# HandschuhProfessionell.net
KiCad netlist of a schematic drawn in EAGLE
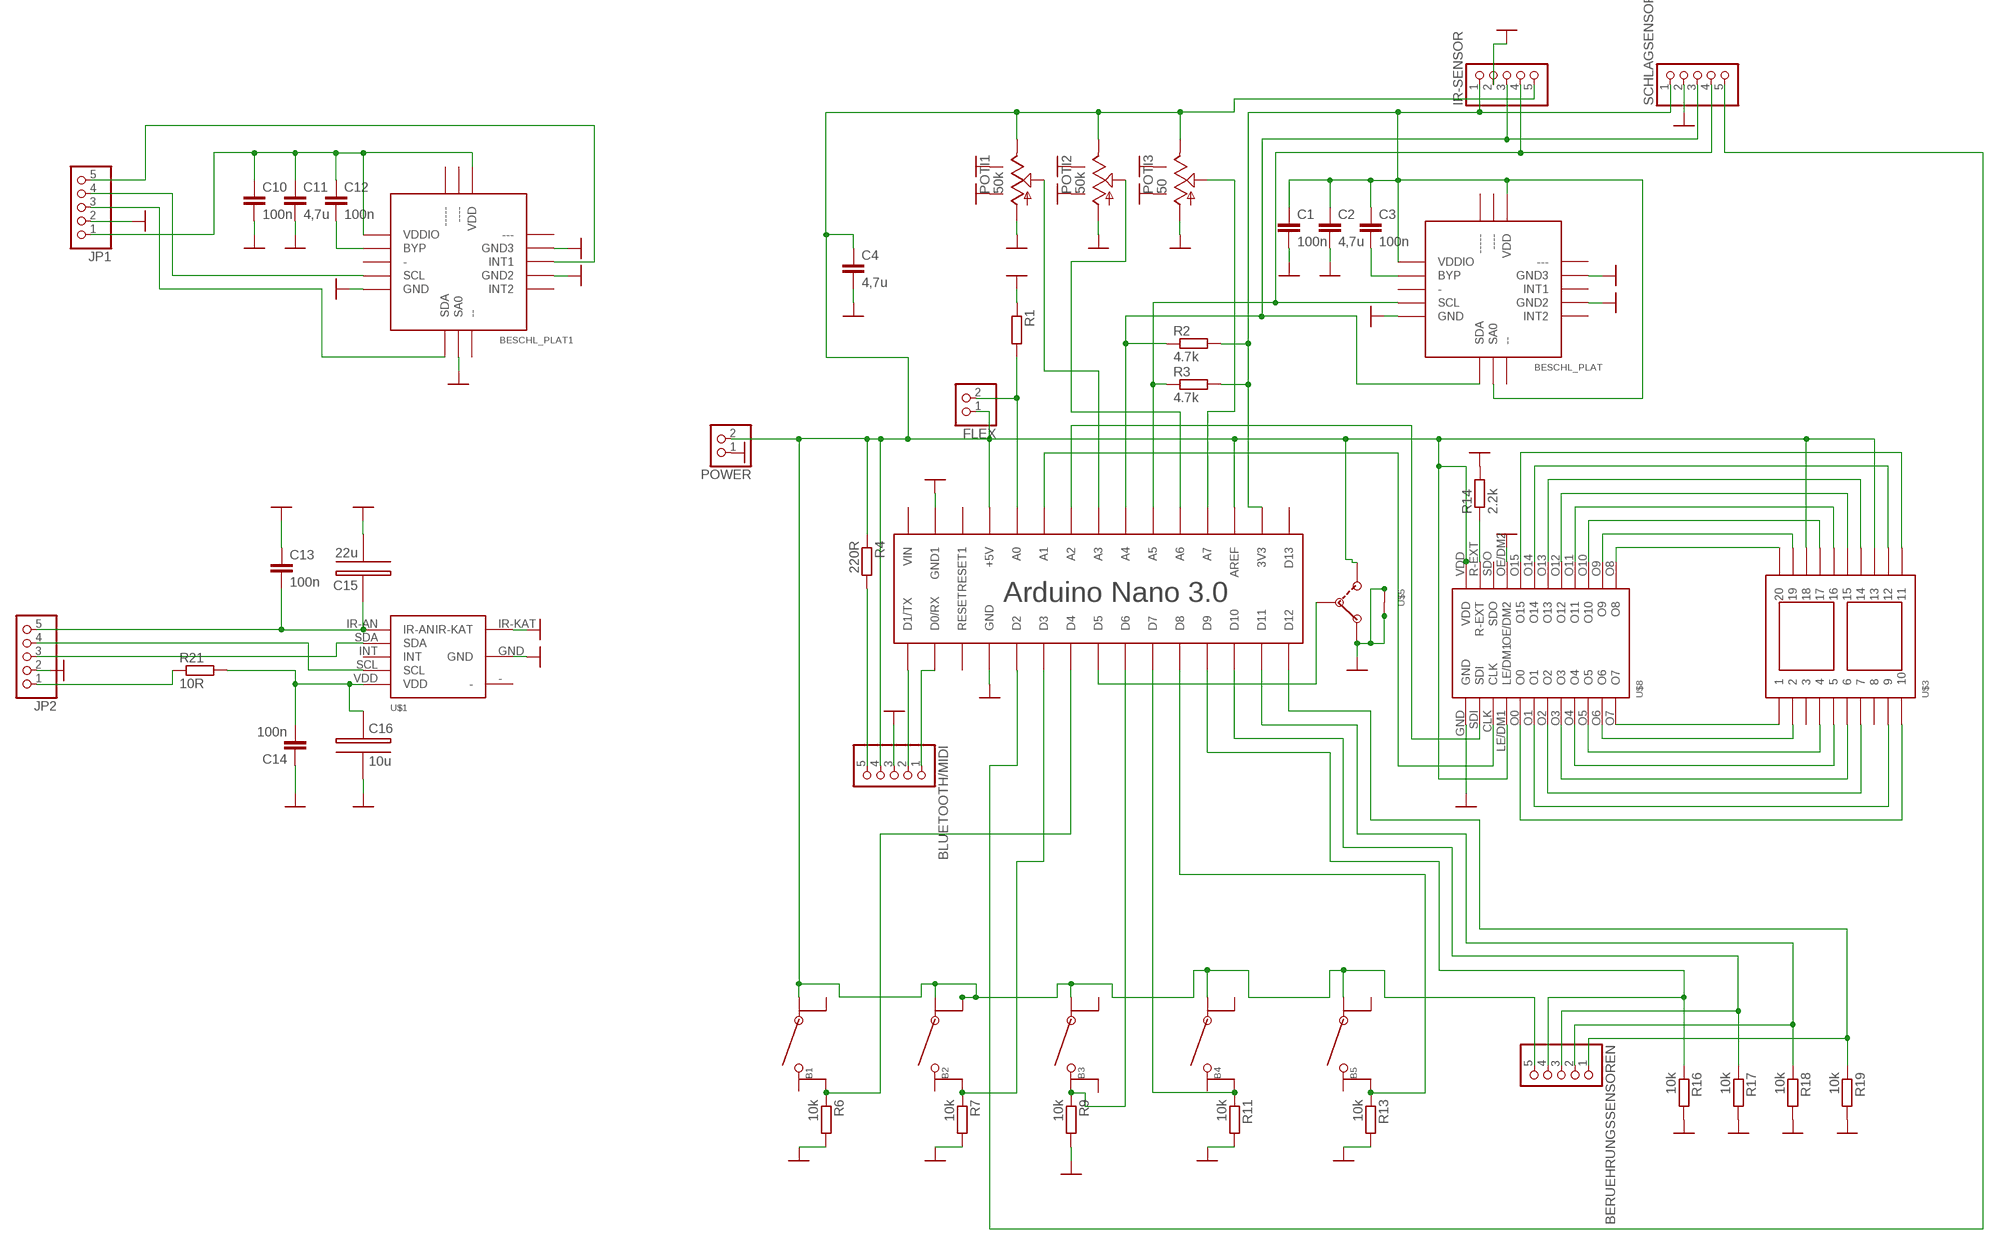
[diagram p0: schematic, sheet 1]

(export (version "E")
  (design (tool "Eeschema 10.0.6"))
  (components
    (comp (ref "B1")
      (value "BUTTON")
      (footprint "eagle-import:BUTTON")
      (libsource (lib "eagle-import") (part "BUTTON"))
    )
    (comp (ref "B2")
      (value "BUTTON")
      (footprint "eagle-import:BUTTON")
      (libsource (lib "eagle-import") (part "BUTTON"))
    )
    (comp (ref "B3")
      (value "BUTTON")
      (footprint "eagle-import:BUTTON")
      (libsource (lib "eagle-import") (part "BUTTON"))
    )
    (comp (ref "B4")
      (value "BUTTON")
      (footprint "eagle-import:BUTTON")
      (libsource (lib "eagle-import") (part "BUTTON"))
    )
    (comp (ref "B5")
      (value "BUTTON")
      (footprint "eagle-import:BUTTON")
      (libsource (lib "eagle-import") (part "BUTTON"))
    )
    (comp (ref "BERUEHRUNGSSENSOREN")
      (value "PINHD-1X5")
      (footprint "eagle-import:1X05")
      (libsource (lib "eagle-import") (part "PINHD-1X5"))
    )
    (comp (ref "BESCHL_PLAT")
      (value "BESCHLEUNIGSUNGSSENSOR")
      (footprint "eagle-import:BESCHLEUNIGUNGSSENSOR")
      (libsource (lib "eagle-import") (part "BESCHLEUNIGSUNGSSENSOR"))
    )
    (comp (ref "BESCHL_PLAT1")
      (value "BESCHLEUNIGSUNGSSENSOR")
      (footprint "eagle-import:BESCHLEUNIGUNGSSENSOR")
      (libsource (lib "eagle-import") (part "BESCHLEUNIGSUNGSSENSOR"))
    )
    (comp (ref "BLUETOOTH/MIDI")
      (value "PINHD-1X5")
      (footprint "eagle-import:1X05")
      (libsource (lib "eagle-import") (part "PINHD-1X5"))
    )
    (comp (ref "C1")
      (value "100n")
      (footprint "eagle-import:C0805")
      (libsource (lib "eagle-import") (part "C-EUC0805"))
    )
    (comp (ref "C2")
      (value "4,7u")
      (footprint "eagle-import:C0805")
      (libsource (lib "eagle-import") (part "C-EUC0805"))
    )
    (comp (ref "C3")
      (value "100n")
      (footprint "eagle-import:C0805")
      (libsource (lib "eagle-import") (part "C-EUC0805"))
    )
    (comp (ref "C4")
      (value "4,7u")
      (footprint "eagle-import:C0805")
      (libsource (lib "eagle-import") (part "C-EUC0805"))
    )
    (comp (ref "C10")
      (value "100n")
      (footprint "eagle-import:C0805")
      (libsource (lib "eagle-import") (part "C-EUC0805"))
    )
    (comp (ref "C11")
      (value "4,7u")
      (footprint "eagle-import:C0805")
      (libsource (lib "eagle-import") (part "C-EUC0805"))
    )
    (comp (ref "C12")
      (value "100n")
      (footprint "eagle-import:C0805")
      (libsource (lib "eagle-import") (part "C-EUC0805"))
    )
    (comp (ref "C13")
      (value "100n")
      (footprint "eagle-import:C0805")
      (libsource (lib "eagle-import") (part "C-EUC0805"))
    )
    (comp (ref "C14")
      (value "100n")
      (footprint "eagle-import:C0805")
      (libsource (lib "eagle-import") (part "C-EUC0805"))
    )
    (comp (ref "C15")
      (value "22u")
      (footprint "eagle-import:22U-KONDENSATOR")
      (libsource (lib "eagle-import") (part "22U-KONDENSATOR"))
    )
    (comp (ref "C16")
      (value "10u")
      (footprint "eagle-import:22U-KONDENSATOR")
      (libsource (lib "eagle-import") (part "22U-KONDENSATOR"))
    )
    (comp (ref "FLEX")
      (value "PINHD-1X2")
      (footprint "eagle-import:1X02")
      (libsource (lib "eagle-import") (part "PINHD-1X2"))
    )
    (comp (ref "IR-SENSOR")
      (value "PINHD-1X5")
      (footprint "eagle-import:1X05")
      (libsource (lib "eagle-import") (part "PINHD-1X5"))
    )
    (comp (ref "JP1")
      (value "PINHD-1X5")
      (footprint "eagle-import:1X05")
      (libsource (lib "eagle-import") (part "PINHD-1X5"))
    )
    (comp (ref "JP2")
      (value "PINHD-1X5/90")
      (footprint "eagle-import:1X05_90")
      (libsource (lib "eagle-import") (part "pinhead_wurz-kompatibel_PINHD-1X5/90"))
    )
    (comp (ref "POTI1")
      (value "50k")
      (footprint "eagle-import:POTI")
      (libsource (lib "eagle-import") (part "POTI"))
    )
    (comp (ref "POTI2")
      (value "50k")
      (footprint "eagle-import:POTI")
      (libsource (lib "eagle-import") (part "POTI"))
    )
    (comp (ref "POTI3")
      (value "50")
      (footprint "eagle-import:POTI")
      (libsource (lib "eagle-import") (part "POTI"))
    )
    (comp (ref "POWER")
      (value "PINHD-1X2")
      (footprint "eagle-import:1X02")
      (libsource (lib "eagle-import") (part "PINHD-1X2"))
    )
    (comp (ref "R1")
      (value "R-EU_M0805")
      (footprint "eagle-import:M0805")
      (libsource (lib "eagle-import") (part "R-EU_M0805"))
    )
    (comp (ref "R2")
      (value "4.7k")
      (footprint "eagle-import:M0805")
      (libsource (lib "eagle-import") (part "R-EU_M0805"))
    )
    (comp (ref "R3")
      (value "4.7k")
      (footprint "eagle-import:M0805")
      (libsource (lib "eagle-import") (part "R-EU_M0805"))
    )
    (comp (ref "R4")
      (value "220R")
      (footprint "eagle-import:M0805")
      (libsource (lib "eagle-import") (part "R-EU_M0805"))
    )
    (comp (ref "R6")
      (value "10k")
      (footprint "eagle-import:M0805")
      (libsource (lib "eagle-import") (part "R-EU_M0805"))
    )
    (comp (ref "R7")
      (value "10k")
      (footprint "eagle-import:M0805")
      (libsource (lib "eagle-import") (part "R-EU_M0805"))
    )
    (comp (ref "R9")
      (value "10k")
      (footprint "eagle-import:M0805")
      (libsource (lib "eagle-import") (part "R-EU_M0805"))
    )
    (comp (ref "R11")
      (value "10k")
      (footprint "eagle-import:M0805")
      (libsource (lib "eagle-import") (part "R-EU_M0805"))
    )
    (comp (ref "R13")
      (value "10k")
      (footprint "eagle-import:M0805")
      (libsource (lib "eagle-import") (part "R-EU_M0805"))
    )
    (comp (ref "R14")
      (value "2.2k")
      (footprint "eagle-import:M0805")
      (libsource (lib "eagle-import") (part "R-EU_M0805"))
    )
    (comp (ref "R16")
      (value "10k")
      (footprint "eagle-import:M0805")
      (libsource (lib "eagle-import") (part "R-EU_M0805"))
    )
    (comp (ref "R17")
      (value "10k")
      (footprint "eagle-import:M0805")
      (libsource (lib "eagle-import") (part "R-EU_M0805"))
    )
    (comp (ref "R18")
      (value "10k")
      (footprint "eagle-import:M0805")
      (libsource (lib "eagle-import") (part "R-EU_M0805"))
    )
    (comp (ref "R19")
      (value "10k")
      (footprint "eagle-import:M0805")
      (libsource (lib "eagle-import") (part "R-EU_M0805"))
    )
    (comp (ref "R21")
      (value "10R")
      (footprint "eagle-import:M0805")
      (libsource (lib "eagle-import") (part "R-EU_M0805"))
    )
    (comp (ref "SCHLAGSENSOR")
      (value "PINHD-1X5")
      (footprint "eagle-import:1X05")
      (libsource (lib "eagle-import") (part "PINHD-1X5"))
    )
    (comp (ref "U$1")
      (value "IR-SENSOR")
      (footprint "eagle-import:IR-SENSOR")
      (libsource (lib "eagle-import") (part "IR-SENSOR"))
    )
    (comp (ref "U$2")
      (value "ARDUINONANO")
      (footprint "eagle-import:PDIP-32")
      (libsource (lib "eagle-import") (part "ARDUINONANO"))
    )
    (comp (ref "U$3")
      (value "7-SEGMENT")
      (footprint "eagle-import:7-SEGMENT")
      (libsource (lib "eagle-import") (part "7-SEGMENT"))
    )
    (comp (ref "U$5")
      (value "SCHALTER")
      (footprint "eagle-import:SCHALTER")
      (libsource (lib "eagle-import") (part "SCHALTER"))
    )
    (comp (ref "U$8")
      (value "7-SEGMENT-TREIBER")
      (footprint "eagle-import:7-SEGMENT-TREIBER")
      (libsource (lib "eagle-import") (part "7-SEGMENT-TREIBER"))
    )
  )
  (nets
    (net (code "1") (name "Net-(B1-Pad2)") (class "Default")
      (node (ref "B1") (pin "2") (pinfunction "2_2") (pintype "bidirectional"))
      (node (ref "R6") (pin "1") (pinfunction "1_1") (pintype "passive"))
      (node (ref "U$2") (pin "D4") (pinfunction "D4_D4") (pintype "bidirectional"))
    )
    (net (code "2") (name "Net-(B1-Pad3)") (class "Default")
      (node (ref "B1") (pin "3") (pinfunction "3_3") (pintype "bidirectional"))
      (node (ref "B2") (pin "3") (pinfunction "3_3") (pintype "bidirectional"))
      (node (ref "B2") (pin "4") (pinfunction "4_4") (pintype "bidirectional"))
      (node (ref "B3") (pin "3") (pinfunction "3_3") (pintype "bidirectional"))
      (node (ref "B4") (pin "3") (pinfunction "3_3") (pintype "bidirectional"))
      (node (ref "B5") (pin "3") (pinfunction "3_3") (pintype "bidirectional"))
      (node (ref "BERUEHRUNGSSENSOREN") (pin "5") (pinfunction "5_5") (pintype "passive"))
      (node (ref "BLUETOOTH/MIDI") (pin "4") (pinfunction "4_4") (pintype "passive"))
      (node (ref "C4") (pin "1") (pinfunction "1_1") (pintype "passive"))
      (node (ref "FLEX") (pin "1") (pinfunction "1_1") (pintype "passive"))
      (node (ref "IR-SENSOR") (pin "5") (pinfunction "5_5") (pintype "passive"))
      (node (ref "POTI1") (pin "VCC") (pinfunction "VCC_VCC") (pintype "passive"))
      (node (ref "POTI2") (pin "VCC") (pinfunction "VCC_VCC") (pintype "passive"))
      (node (ref "POTI3") (pin "VCC") (pinfunction "VCC_VCC") (pintype "passive"))
      (node (ref "POWER") (pin "2") (pinfunction "2_2") (pintype "passive"))
      (node (ref "R4") (pin "1") (pinfunction "1_1") (pintype "passive"))
      (node (ref "U$2") (pin "+5V") (pinfunction "+5V_+5V") (pintype "bidirectional"))
      (node (ref "U$2") (pin "AREF") (pinfunction "AREF_AREF") (pintype "bidirectional"))
      (node (ref "U$3") (pin "13") (pinfunction "13_13") (pintype "bidirectional"))
      (node (ref "U$3") (pin "18") (pinfunction "18_18") (pintype "bidirectional"))
      (node (ref "U$5") (pin "3") (pinfunction "3_3") (pintype "bidirectional"))
      (node (ref "U$8") (pin "LE/DM1") (pinfunction "LE/DM1_LE/DM1") (pintype "bidirectional"))
      (node (ref "U$8") (pin "VDD") (pinfunction "VDD_VDD") (pintype "bidirectional"))
    )
    (net (code "3") (name "Net-(B2-Pad2)") (class "Default")
      (node (ref "B2") (pin "2") (pinfunction "2_2") (pintype "bidirectional"))
      (node (ref "R7") (pin "1") (pinfunction "1_1") (pintype "passive"))
      (node (ref "U$2") (pin "D3") (pinfunction "D3_D3") (pintype "bidirectional"))
    )
    (net (code "4") (name "Net-(B3-Pad1)") (class "Default")
      (node (ref "B3") (pin "1") (pinfunction "1_1") (pintype "bidirectional"))
      (node (ref "R9") (pin "1") (pinfunction "1_1") (pintype "passive"))
      (node (ref "U$2") (pin "D6") (pinfunction "D6_D6") (pintype "bidirectional"))
    )
    (net (code "5") (name "Net-(B4-Pad2)") (class "Default")
      (node (ref "B4") (pin "2") (pinfunction "2_2") (pintype "bidirectional"))
      (node (ref "R11") (pin "1") (pinfunction "1_1") (pintype "passive"))
      (node (ref "U$2") (pin "D7") (pinfunction "D7_D7") (pintype "bidirectional"))
    )
    (net (code "6") (name "Net-(B5-Pad2)") (class "Default")
      (node (ref "B5") (pin "2") (pinfunction "2_2") (pintype "bidirectional"))
      (node (ref "R13") (pin "1") (pinfunction "1_1") (pintype "passive"))
      (node (ref "U$2") (pin "D8") (pinfunction "D8_D8") (pintype "bidirectional"))
    )
    (net (code "7") (name "Net-(BERUEHRUNGSSENSOREN-Pad1)") (class "Default")
      (node (ref "BERUEHRUNGSSENSOREN") (pin "1") (pinfunction "1_1") (pintype "passive"))
      (node (ref "R19") (pin "1") (pinfunction "1_1") (pintype "passive"))
      (node (ref "U$2") (pin "D12") (pinfunction "D12_D12") (pintype "bidirectional"))
    )
    (net (code "8") (name "Net-(BERUEHRUNGSSENSOREN-Pad2)") (class "Default")
      (node (ref "BERUEHRUNGSSENSOREN") (pin "2") (pinfunction "2_2") (pintype "passive"))
      (node (ref "R18") (pin "1") (pinfunction "1_1") (pintype "passive"))
      (node (ref "U$2") (pin "D11") (pinfunction "D11_D11") (pintype "bidirectional"))
    )
    (net (code "9") (name "Net-(BERUEHRUNGSSENSOREN-Pad3)") (class "Default")
      (node (ref "BERUEHRUNGSSENSOREN") (pin "3") (pinfunction "3_3") (pintype "passive"))
      (node (ref "R17") (pin "1") (pinfunction "1_1") (pintype "passive"))
      (node (ref "U$2") (pin "D10") (pinfunction "D10_D10") (pintype "bidirectional"))
    )
    (net (code "10") (name "Net-(BERUEHRUNGSSENSOREN-Pad4)") (class "Default")
      (node (ref "BERUEHRUNGSSENSOREN") (pin "4") (pinfunction "4_4") (pintype "passive"))
      (node (ref "R16") (pin "1") (pinfunction "1_1") (pintype "passive"))
      (node (ref "U$2") (pin "D9") (pinfunction "D9_D9") (pintype "bidirectional"))
    )
    (net (code "11") (name "Net-(BESCHL_PLAT-PadBYP)") (class "Default")
      (node (ref "BESCHL_PLAT") (pin "BYP") (pinfunction "BYP_BYP") (pintype "bidirectional"))
      (node (ref "C3") (pin "2") (pinfunction "2_2") (pintype "passive"))
    )
    (net (code "12") (name "Net-(BESCHL_PLAT-PadSA0)") (class "Default")
      (node (ref "BESCHL_PLAT") (pin "SA0") (pinfunction "SA0_SA0") (pintype "bidirectional"))
      (node (ref "BESCHL_PLAT") (pin "VDD") (pinfunction "VDD_VDD") (pintype "bidirectional"))
      (node (ref "BESCHL_PLAT") (pin "VDDIO") (pinfunction "VDDIO_VDDIO") (pintype "bidirectional"))
      (node (ref "C1") (pin "1") (pinfunction "1_1") (pintype "passive"))
      (node (ref "C2") (pin "1") (pinfunction "1_1") (pintype "passive"))
      (node (ref "C3") (pin "1") (pinfunction "1_1") (pintype "passive"))
      (node (ref "IR-SENSOR") (pin "1") (pinfunction "1_1") (pintype "passive"))
      (node (ref "R2") (pin "2") (pinfunction "2_2") (pintype "passive"))
      (node (ref "R3") (pin "2") (pinfunction "2_2") (pintype "passive"))
      (node (ref "SCHLAGSENSOR") (pin "1") (pinfunction "1_1") (pintype "passive"))
      (node (ref "U$2") (pin "3V3") (pinfunction "3V3_3V3") (pintype "bidirectional"))
    )
    (net (code "13") (name "Net-(BESCHL_PLAT-PadSCL)") (class "Default")
      (node (ref "BESCHL_PLAT") (pin "SCL") (pinfunction "SCL_SCL") (pintype "bidirectional"))
      (node (ref "IR-SENSOR") (pin "4") (pinfunction "4_4") (pintype "passive"))
      (node (ref "R3") (pin "1") (pinfunction "1_1") (pintype "passive"))
      (node (ref "SCHLAGSENSOR") (pin "4") (pinfunction "4_4") (pintype "passive"))
      (node (ref "U$2") (pin "A5") (pinfunction "A5_A5") (pintype "bidirectional"))
    )
    (net (code "14") (name "Net-(BESCHL_PLAT-PadSDA)") (class "Default")
      (node (ref "BESCHL_PLAT") (pin "SDA") (pinfunction "SDA_SDA") (pintype "bidirectional"))
      (node (ref "IR-SENSOR") (pin "3") (pinfunction "3_3") (pintype "passive"))
      (node (ref "R2") (pin "1") (pinfunction "1_1") (pintype "passive"))
      (node (ref "SCHLAGSENSOR") (pin "3") (pinfunction "3_3") (pintype "passive"))
      (node (ref "U$2") (pin "A4") (pinfunction "A4_A4") (pintype "bidirectional"))
    )
    (net (code "15") (name "Net-(BESCHL_PLAT1-PadBYP)") (class "Default")
      (node (ref "BESCHL_PLAT1") (pin "BYP") (pinfunction "BYP_BYP") (pintype "bidirectional"))
      (node (ref "C12") (pin "2") (pinfunction "2_2") (pintype "passive"))
    )
    (net (code "16") (name "Net-(BESCHL_PLAT1-PadINT1)") (class "Default")
      (node (ref "BESCHL_PLAT1") (pin "INT1") (pinfunction "INT1_INT1") (pintype "bidirectional"))
      (node (ref "JP1") (pin "5") (pinfunction "5_5") (pintype "passive"))
    )
    (net (code "17") (name "Net-(BESCHL_PLAT1-PadSCL)") (class "Default")
      (node (ref "BESCHL_PLAT1") (pin "SCL") (pinfunction "SCL_SCL") (pintype "bidirectional"))
      (node (ref "JP1") (pin "4") (pinfunction "4_4") (pintype "passive"))
    )
    (net (code "18") (name "Net-(BESCHL_PLAT1-PadSDA)") (class "Default")
      (node (ref "BESCHL_PLAT1") (pin "SDA") (pinfunction "SDA_SDA") (pintype "bidirectional"))
      (node (ref "JP1") (pin "3") (pinfunction "3_3") (pintype "passive"))
    )
    (net (code "19") (name "Net-(BESCHL_PLAT1-PadVDD)") (class "Default")
      (node (ref "BESCHL_PLAT1") (pin "VDD") (pinfunction "VDD_VDD") (pintype "bidirectional"))
      (node (ref "BESCHL_PLAT1") (pin "VDDIO") (pinfunction "VDDIO_VDDIO") (pintype "bidirectional"))
      (node (ref "C10") (pin "1") (pinfunction "1_1") (pintype "passive"))
      (node (ref "C11") (pin "1") (pinfunction "1_1") (pintype "passive"))
      (node (ref "C12") (pin "1") (pinfunction "1_1") (pintype "passive"))
      (node (ref "JP1") (pin "1") (pinfunction "1_1") (pintype "passive"))
    )
    (net (code "20") (name "Net-(BLUETOOTH/MIDI-Pad1)") (class "Default")
      (node (ref "BLUETOOTH/MIDI") (pin "1") (pinfunction "1_1") (pintype "passive"))
      (node (ref "U$2") (pin "D0/RX") (pinfunction "D0/RX_D0/RX") (pintype "bidirectional"))
    )
    (net (code "21") (name "Net-(BLUETOOTH/MIDI-Pad2)") (class "Default")
      (node (ref "BLUETOOTH/MIDI") (pin "2") (pinfunction "2_2") (pintype "passive"))
      (node (ref "U$2") (pin "D1/TX") (pinfunction "D1/TX_D1/TX") (pintype "bidirectional"))
    )
    (net (code "22") (name "Net-(BLUETOOTH/MIDI-Pad5)") (class "Default")
      (node (ref "BLUETOOTH/MIDI") (pin "5") (pinfunction "5_5") (pintype "passive"))
      (node (ref "R4") (pin "2") (pinfunction "2_2") (pintype "passive"))
    )
    (net (code "23") (name "Net-(C13-Pad2)") (class "Default")
      (node (ref "C13") (pin "2") (pinfunction "2_2") (pintype "passive"))
      (node (ref "C15") (pin "+") (pinfunction "+_+") (pintype "bidirectional"))
      (node (ref "JP2") (pin "5") (pinfunction "5_5") (pintype "passive"))
      (node (ref "U$1") (pin "IR-AN") (pinfunction "IR-AN_IR-AN") (pintype "bidirectional"))
    )
    (net (code "24") (name "Net-(C14-Pad2)") (class "Default")
      (node (ref "C14") (pin "2") (pinfunction "2_2") (pintype "passive"))
      (node (ref "C16") (pin "+") (pinfunction "+_+") (pintype "bidirectional"))
      (node (ref "R21") (pin "2") (pinfunction "2_2") (pintype "passive"))
      (node (ref "U$1") (pin "VDD") (pinfunction "VDD_VDD") (pintype "bidirectional"))
    )
    (net (code "25") (name "Net-(FLEX-Pad2)") (class "Default")
      (node (ref "FLEX") (pin "2") (pinfunction "2_2") (pintype "passive"))
      (node (ref "R1") (pin "2") (pinfunction "2_2") (pintype "passive"))
      (node (ref "U$2") (pin "A0") (pinfunction "A0_A0") (pintype "bidirectional"))
    )
    (net (code "26") (name "Net-(JP2-Pad1)") (class "Default")
      (node (ref "JP2") (pin "1") (pinfunction "1_1") (pintype "passive"))
      (node (ref "R21") (pin "1") (pinfunction "1_1") (pintype "passive"))
    )
    (net (code "27") (name "Net-(JP2-Pad3)") (class "Default")
      (node (ref "JP2") (pin "3") (pinfunction "3_3") (pintype "passive"))
      (node (ref "U$1") (pin "SDA") (pinfunction "SDA_SDA") (pintype "bidirectional"))
    )
    (net (code "28") (name "Net-(JP2-Pad4)") (class "Default")
      (node (ref "JP2") (pin "4") (pinfunction "4_4") (pintype "passive"))
      (node (ref "U$1") (pin "SCL") (pinfunction "SCL_SCL") (pintype "bidirectional"))
    )
    (net (code "29") (name "Net-(POTI1-PadVALUE)") (class "Default")
      (node (ref "POTI1") (pin "VALUE") (pinfunction "VALUE_VALUE") (pintype "passive"))
      (node (ref "U$2") (pin "A3") (pinfunction "A3_A3") (pintype "bidirectional"))
    )
    (net (code "30") (name "Net-(POTI2-PadVALUE)") (class "Default")
      (node (ref "POTI2") (pin "VALUE") (pinfunction "VALUE_VALUE") (pintype "passive"))
      (node (ref "U$2") (pin "A6") (pinfunction "A6_A6") (pintype "bidirectional"))
    )
    (net (code "31") (name "Net-(POTI3-PadVALUE)") (class "Default")
      (node (ref "POTI3") (pin "VALUE") (pinfunction "VALUE_VALUE") (pintype "passive"))
      (node (ref "U$2") (pin "A7") (pinfunction "A7_A7") (pintype "bidirectional"))
    )
    (net (code "32") (name "Net-(R14-Pad1)") (class "Default")
      (node (ref "R14") (pin "1") (pinfunction "1_1") (pintype "passive"))
      (node (ref "U$8") (pin "R-EXT") (pinfunction "R-EXT_R-EXT") (pintype "bidirectional"))
    )
    (net (code "33") (name "Net-(SCHLAGSENSOR-Pad5)") (class "Default")
      (node (ref "SCHLAGSENSOR") (pin "5") (pinfunction "5_5") (pintype "passive"))
      (node (ref "U$2") (pin "D2") (pinfunction "D2_D2") (pintype "bidirectional"))
    )
    (net (code "34") (name "Net-(U$2-PadA1)") (class "Default")
      (node (ref "U$2") (pin "A1") (pinfunction "A1_A1") (pintype "bidirectional"))
      (node (ref "U$8") (pin "CLK") (pinfunction "CLK_CLK") (pintype "bidirectional"))
    )
    (net (code "35") (name "Net-(U$2-PadA2)") (class "Default")
      (node (ref "U$2") (pin "A2") (pinfunction "A2_A2") (pintype "bidirectional"))
      (node (ref "U$8") (pin "SDI") (pinfunction "SDI_SDI") (pintype "bidirectional"))
    )
    (net (code "36") (name "Net-(U$2-PadD5)") (class "Default")
      (node (ref "U$2") (pin "D5") (pinfunction "D5_D5") (pintype "bidirectional"))
      (node (ref "U$5") (pin "2") (pinfunction "2_2") (pintype "bidirectional"))
    )
    (net (code "37") (name "Net-(U$3-Pad1)") (class "Default")
      (node (ref "U$3") (pin "1") (pinfunction "1_1") (pintype "bidirectional"))
      (node (ref "U$8") (pin "O7") (pinfunction "O7_O7") (pintype "bidirectional"))
    )
    (net (code "38") (name "Net-(U$3-Pad2)") (class "Default")
      (node (ref "U$3") (pin "2") (pinfunction "2_2") (pintype "bidirectional"))
      (node (ref "U$8") (pin "O6") (pinfunction "O6_O6") (pintype "bidirectional"))
    )
    (net (code "39") (name "Net-(U$3-Pad4)") (class "Default")
      (node (ref "U$3") (pin "4") (pinfunction "4_4") (pintype "bidirectional"))
      (node (ref "U$8") (pin "O5") (pinfunction "O5_O5") (pintype "bidirectional"))
    )
    (net (code "40") (name "Net-(U$3-Pad5)") (class "Default")
      (node (ref "U$3") (pin "5") (pinfunction "5_5") (pintype "bidirectional"))
      (node (ref "U$8") (pin "O4") (pinfunction "O4_O4") (pintype "bidirectional"))
    )
    (net (code "41") (name "Net-(U$3-Pad6)") (class "Default")
      (node (ref "U$3") (pin "6") (pinfunction "6_6") (pintype "bidirectional"))
      (node (ref "U$8") (pin "O3") (pinfunction "O3_O3") (pintype "bidirectional"))
    )
    (net (code "42") (name "Net-(U$3-Pad7)") (class "Default")
      (node (ref "U$3") (pin "7") (pinfunction "7_7") (pintype "bidirectional"))
      (node (ref "U$8") (pin "O2") (pinfunction "O2_O2") (pintype "bidirectional"))
    )
    (net (code "43") (name "Net-(U$3-Pad9)") (class "Default")
      (node (ref "U$3") (pin "9") (pinfunction "9_9") (pintype "bidirectional"))
      (node (ref "U$8") (pin "O1") (pinfunction "O1_O1") (pintype "bidirectional"))
    )
    (net (code "44") (name "Net-(U$3-Pad10)") (class "Default")
      (node (ref "U$3") (pin "10") (pinfunction "10_10") (pintype "bidirectional"))
      (node (ref "U$8") (pin "O0") (pinfunction "O0_O0") (pintype "bidirectional"))
    )
    (net (code "45") (name "Net-(U$3-Pad11)") (class "Default")
      (node (ref "U$3") (pin "11") (pinfunction "11_11") (pintype "bidirectional"))
      (node (ref "U$8") (pin "O15") (pinfunction "O15_O15") (pintype "bidirectional"))
    )
    (net (code "46") (name "Net-(U$3-Pad12)") (class "Default")
      (node (ref "U$3") (pin "12") (pinfunction "12_12") (pintype "bidirectional"))
      (node (ref "U$8") (pin "O14") (pinfunction "O14_O14") (pintype "bidirectional"))
    )
    (net (code "47") (name "Net-(U$3-Pad14)") (class "Default")
      (node (ref "U$3") (pin "14") (pinfunction "14_14") (pintype "bidirectional"))
      (node (ref "U$8") (pin "O13") (pinfunction "O13_O13") (pintype "bidirectional"))
    )
    (net (code "48") (name "Net-(U$3-Pad15)") (class "Default")
      (node (ref "U$3") (pin "15") (pinfunction "15_15") (pintype "bidirectional"))
      (node (ref "U$8") (pin "O12") (pinfunction "O12_O12") (pintype "bidirectional"))
    )
    (net (code "49") (name "Net-(U$3-Pad16)") (class "Default")
      (node (ref "U$3") (pin "16") (pinfunction "16_16") (pintype "bidirectional"))
      (node (ref "U$8") (pin "O11") (pinfunction "O11_O11") (pintype "bidirectional"))
    )
    (net (code "50") (name "Net-(U$3-Pad17)") (class "Default")
      (node (ref "U$3") (pin "17") (pinfunction "17_17") (pintype "bidirectional"))
      (node (ref "U$8") (pin "O10") (pinfunction "O10_O10") (pintype "bidirectional"))
    )
    (net (code "51") (name "Net-(U$3-Pad19)") (class "Default")
      (node (ref "U$3") (pin "19") (pinfunction "19_19") (pintype "bidirectional"))
      (node (ref "U$8") (pin "O9") (pinfunction "O9_O9") (pintype "bidirectional"))
    )
    (net (code "52") (name "Net-(U$3-Pad20)") (class "Default")
      (node (ref "U$3") (pin "20") (pinfunction "20_20") (pintype "bidirectional"))
      (node (ref "U$8") (pin "O8") (pinfunction "O8_O8") (pintype "bidirectional"))
    )
    (net (code "53") (name "POWER_SUPPLY1_GND") (class "Default")
      (node (ref "BESCHL_PLAT") (pin "GND") (pinfunction "GND_GND") (pintype "bidirectional"))
      (node (ref "BESCHL_PLAT") (pin "GND2") (pinfunction "GND2_GND2") (pintype "bidirectional"))
      (node (ref "BESCHL_PLAT") (pin "GND3") (pinfunction "GND3_GND3") (pintype "bidirectional"))
      (node (ref "BESCHL_PLAT1") (pin "GND") (pinfunction "GND_GND") (pintype "bidirectional"))
      (node (ref "BESCHL_PLAT1") (pin "GND2") (pinfunction "GND2_GND2") (pintype "bidirectional"))
      (node (ref "BESCHL_PLAT1") (pin "GND3") (pinfunction "GND3_GND3") (pintype "bidirectional"))
      (node (ref "BESCHL_PLAT1") (pin "SA0") (pinfunction "SA0_SA0") (pintype "bidirectional"))
      (node (ref "BLUETOOTH/MIDI") (pin "3") (pinfunction "3_3") (pintype "passive"))
      (node (ref "C1") (pin "2") (pinfunction "2_2") (pintype "passive"))
      (node (ref "C10") (pin "2") (pinfunction "2_2") (pintype "passive"))
      (node (ref "C11") (pin "2") (pinfunction "2_2") (pintype "passive"))
      (node (ref "C13") (pin "1") (pinfunction "1_1") (pintype "passive"))
      (node (ref "C14") (pin "1") (pinfunction "1_1") (pintype "passive"))
      (node (ref "C15") (pin "-") (pinfunction "-_-") (pintype "bidirectional"))
      (node (ref "C16") (pin "-") (pinfunction "-_-") (pintype "bidirectional"))
      (node (ref "C2") (pin "2") (pinfunction "2_2") (pintype "passive"))
      (node (ref "C4") (pin "2") (pinfunction "2_2") (pintype "passive"))
      (node (ref "IR-SENSOR") (pin "2") (pinfunction "2_2") (pintype "passive"))
      (node (ref "JP1") (pin "2") (pinfunction "2_2") (pintype "passive"))
      (node (ref "JP2") (pin "2") (pinfunction "2_2") (pintype "passive"))
      (node (ref "POTI1") (pin "FIX1") (pinfunction "FUSS1_FIX1") (pintype "passive"))
      (node (ref "POTI1") (pin "FIX2") (pinfunction "FUSS2_FIX2") (pintype "passive"))
      (node (ref "POTI1") (pin "GND") (pinfunction "GND_GND") (pintype "passive"))
      (node (ref "POTI2") (pin "FIX1") (pinfunction "FUSS1_FIX1") (pintype "passive"))
      (node (ref "POTI2") (pin "FIX2") (pinfunction "FUSS2_FIX2") (pintype "passive"))
      (node (ref "POTI2") (pin "GND") (pinfunction "GND_GND") (pintype "passive"))
      (node (ref "POTI3") (pin "FIX1") (pinfunction "FUSS1_FIX1") (pintype "passive"))
      (node (ref "POTI3") (pin "FIX2") (pinfunction "FUSS2_FIX2") (pintype "passive"))
      (node (ref "POTI3") (pin "GND") (pinfunction "GND_GND") (pintype "passive"))
      (node (ref "POWER") (pin "1") (pinfunction "1_1") (pintype "passive"))
      (node (ref "R1") (pin "1") (pinfunction "1_1") (pintype "passive"))
      (node (ref "R11") (pin "2") (pinfunction "2_2") (pintype "passive"))
      (node (ref "R13") (pin "2") (pinfunction "2_2") (pintype "passive"))
      (node (ref "R14") (pin "2") (pinfunction "2_2") (pintype "passive"))
      (node (ref "R16") (pin "2") (pinfunction "2_2") (pintype "passive"))
      (node (ref "R17") (pin "2") (pinfunction "2_2") (pintype "passive"))
      (node (ref "R18") (pin "2") (pinfunction "2_2") (pintype "passive"))
      (node (ref "R19") (pin "2") (pinfunction "2_2") (pintype "passive"))
      (node (ref "R6") (pin "2") (pinfunction "2_2") (pintype "passive"))
      (node (ref "R7") (pin "2") (pinfunction "2_2") (pintype "passive"))
      (node (ref "R9") (pin "2") (pinfunction "2_2") (pintype "passive"))
      (node (ref "SCHLAGSENSOR") (pin "2") (pinfunction "2_2") (pintype "passive"))
      (node (ref "U$1") (pin "GND") (pinfunction "GND_GND") (pintype "bidirectional"))
      (node (ref "U$1") (pin "IR-KAT") (pinfunction "IR-KAT_IR-KAT") (pintype "bidirectional"))
      (node (ref "U$2") (pin "GND") (pinfunction "GND_GND") (pintype "bidirectional"))
      (node (ref "U$2") (pin "GND1") (pinfunction "GND1_GND1") (pintype "bidirectional"))
      (node (ref "U$5") (pin "1") (pinfunction "1_1") (pintype "bidirectional"))
      (node (ref "U$5") (pin "4") (pinfunction "4_4") (pintype "bidirectional"))
      (node (ref "U$5") (pin "5") (pinfunction "5_5") (pintype "bidirectional"))
      (node (ref "U$8") (pin "GND") (pinfunction "GND_GND") (pintype "bidirectional"))
      (node (ref "U$8") (pin "OE/DM2") (pinfunction "OE/DM2_OE/DM2") (pintype "bidirectional"))
    )
    (net (code "54") (name "unconnected-(B1-Pad1)") (class "Default")
      (node (ref "B1") (pin "1") (pinfunction "1_1") (pintype "bidirectional"))
    )
    (net (code "55") (name "unconnected-(B1-Pad4)") (class "Default")
      (node (ref "B1") (pin "4") (pinfunction "4_4") (pintype "bidirectional"))
    )
    (net (code "56") (name "unconnected-(B2-Pad1)") (class "Default")
      (node (ref "B2") (pin "1") (pinfunction "1_1") (pintype "bidirectional"))
    )
    (net (code "57") (name "unconnected-(B3-Pad2)") (class "Default")
      (node (ref "B3") (pin "2") (pinfunction "2_2") (pintype "bidirectional"))
    )
    (net (code "58") (name "unconnected-(B3-Pad4)") (class "Default")
      (node (ref "B3") (pin "4") (pinfunction "4_4") (pintype "bidirectional"))
    )
    (net (code "59") (name "unconnected-(B4-Pad1)") (class "Default")
      (node (ref "B4") (pin "1") (pinfunction "1_1") (pintype "bidirectional"))
    )
    (net (code "60") (name "unconnected-(B4-Pad4)") (class "Default")
      (node (ref "B4") (pin "4") (pinfunction "4_4") (pintype "bidirectional"))
    )
    (net (code "61") (name "unconnected-(B5-Pad1)") (class "Default")
      (node (ref "B5") (pin "1") (pinfunction "1_1") (pintype "bidirectional"))
    )
    (net (code "62") (name "unconnected-(B5-Pad4)") (class "Default")
      (node (ref "B5") (pin "4") (pinfunction "4_4") (pintype "bidirectional"))
    )
    (net (code "63") (name "unconnected-(BESCHL_PLAT-Pad-)") (class "Default")
      (node (ref "BESCHL_PLAT") (pin "-") (pinfunction "-_-") (pintype "bidirectional"))
    )
    (net (code "64") (name "unconnected-(BESCHL_PLAT-Pad--)") (class "Default")
      (node (ref "BESCHL_PLAT") (pin "--") (pinfunction "--_--") (pintype "bidirectional"))
    )
    (net (code "65") (name "unconnected-(BESCHL_PLAT-Pad---)") (class "Default")
      (node (ref "BESCHL_PLAT") (pin "---") (pinfunction "---_---") (pintype "bidirectional"))
    )
    (net (code "66") (name "unconnected-(BESCHL_PLAT-Pad----)") (class "Default")
      (node (ref "BESCHL_PLAT") (pin "----") (pinfunction "----_----") (pintype "bidirectional"))
    )
    (net (code "67") (name "unconnected-(BESCHL_PLAT-Pad-----)") (class "Default")
      (node (ref "BESCHL_PLAT") (pin "-----") (pinfunction "-----_-----") (pintype "bidirectional"))
    )
    (net (code "68") (name "unconnected-(BESCHL_PLAT-PadINT1)") (class "Default")
      (node (ref "BESCHL_PLAT") (pin "INT1") (pinfunction "INT1_INT1") (pintype "bidirectional"))
    )
    (net (code "69") (name "unconnected-(BESCHL_PLAT-PadINT2)") (class "Default")
      (node (ref "BESCHL_PLAT") (pin "INT2") (pinfunction "INT2_INT2") (pintype "bidirectional"))
    )
    (net (code "70") (name "unconnected-(BESCHL_PLAT1-Pad-)") (class "Default")
      (node (ref "BESCHL_PLAT1") (pin "-") (pinfunction "-_-") (pintype "bidirectional"))
    )
    (net (code "71") (name "unconnected-(BESCHL_PLAT1-Pad--)") (class "Default")
      (node (ref "BESCHL_PLAT1") (pin "--") (pinfunction "--_--") (pintype "bidirectional"))
    )
    (net (code "72") (name "unconnected-(BESCHL_PLAT1-Pad---)") (class "Default")
      (node (ref "BESCHL_PLAT1") (pin "---") (pinfunction "---_---") (pintype "bidirectional"))
    )
    (net (code "73") (name "unconnected-(BESCHL_PLAT1-Pad----)") (class "Default")
      (node (ref "BESCHL_PLAT1") (pin "----") (pinfunction "----_----") (pintype "bidirectional"))
    )
    (net (code "74") (name "unconnected-(BESCHL_PLAT1-Pad-----)") (class "Default")
      (node (ref "BESCHL_PLAT1") (pin "-----") (pinfunction "-----_-----") (pintype "bidirectional"))
    )
    (net (code "75") (name "unconnected-(BESCHL_PLAT1-PadINT2)") (class "Default")
      (node (ref "BESCHL_PLAT1") (pin "INT2") (pinfunction "INT2_INT2") (pintype "bidirectional"))
    )
    (net (code "76") (name "unconnected-(U$1-Pad-)") (class "Default")
      (node (ref "U$1") (pin "-") (pinfunction "-_-") (pintype "bidirectional"))
    )
    (net (code "77") (name "unconnected-(U$1-PadINT)") (class "Default")
      (node (ref "U$1") (pin "INT") (pinfunction "INT_INT") (pintype "bidirectional"))
    )
    (net (code "78") (name "unconnected-(U$2-PadD13)") (class "Default")
      (node (ref "U$2") (pin "D13") (pinfunction "D13_D13") (pintype "bidirectional"))
    )
    (net (code "79") (name "unconnected-(U$2-PadRESET)") (class "Default")
      (node (ref "U$2") (pin "RESET") (pinfunction "RESET_RESET") (pintype "bidirectional"))
    )
    (net (code "80") (name "unconnected-(U$2-PadRESET1)") (class "Default")
      (node (ref "U$2") (pin "RESET1") (pinfunction "RESET1_RESET1") (pintype "bidirectional"))
    )
    (net (code "81") (name "unconnected-(U$2-PadVIN)") (class "Default")
      (node (ref "U$2") (pin "VIN") (pinfunction "VIN_VIN") (pintype "bidirectional"))
    )
    (net (code "82") (name "unconnected-(U$3-Pad3)") (class "Default")
      (node (ref "U$3") (pin "3") (pinfunction "3_3") (pintype "bidirectional"))
    )
    (net (code "83") (name "unconnected-(U$3-Pad8)") (class "Default")
      (node (ref "U$3") (pin "8") (pinfunction "8_8") (pintype "bidirectional"))
    )
    (net (code "84") (name "unconnected-(U$8-PadSDO)") (class "Default")
      (node (ref "U$8") (pin "SDO") (pinfunction "SDO_SDO") (pintype "bidirectional"))
    )
  )
)
